# MDL_FUENTE_5V.net
KiCad netlist of a schematic drawn in Altium Designer
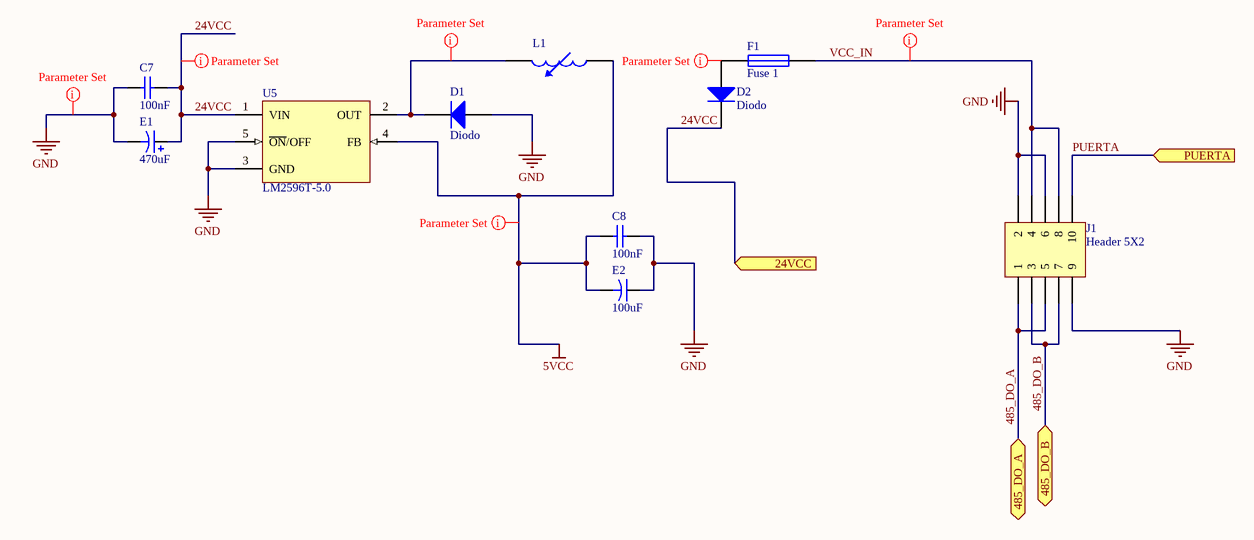
[diagram p0: MDL_FUENTE_5V.SchDoc]

(export (version "E")
  (design (tool "Eeschema 10.0.6"))
  (components
    (comp (ref "C7")
      (value "100nF")
      (footprint "VP44-2.5")
      (description "Dipped Radial Multilayer Ceramic Capacitor X7R: 220nF, 100V")
      (fields (field (name "Comment") "VP44BY224JB") (field (name "PUBLISHER") "Altium Limited"))
      (libsource (lib "Vishay Vitramon Ceramic Dipped Capacitor") (part "VP44BY224JB"))
    )
    (comp (ref "C8")
      (value "100nF")
      (footprint "VP44-2.5")
      (description "Dipped Radial Multilayer Ceramic Capacitor X7R: 220nF, 100V")
      (fields (field (name "Comment") "VP44BY224JB") (field (name "PUBLISHER") "Altium Limited"))
      (libsource (lib "Vishay Vitramon Ceramic Dipped Capacitor") (part "VP44BY224JB"))
    )
    (comp (ref "D1")
      (value "Diodo")
      (footprint "1N4000")
      (description "Diodo rectificador")
      (libsource (lib "Diodos") (part "Diodo"))
    )
    (comp (ref "D2")
      (value "Diodo")
      (footprint "1N4000")
      (description "Diodo rectificador")
      (libsource (lib "Diodos") (part "Diodo"))
    )
    (comp (ref "E1")
      (value "470uF")
      (footprint "C1000UF")
      (description "Polarized Capacitor (Radial)")
      (fields (field (name "Comment") "Cap Pol1") (field (name "PUBLISHER") "Altium Limited"))
      (libsource (lib "Miscellaneous Devices") (part "Cap Pol1"))
    )
    (comp (ref "E2")
      (value "100uF")
      (footprint "C1UF")
      (description "Capacitor")
      (fields (field (name "Comment") "Cap2") (field (name "PUBLISHER") "Altium Limited"))
      (libsource (lib "Miscellaneous Devices") (part "Cap2"))
    )
    (comp (ref "F1")
      (value "Fuse 1")
      (footprint "FUSIBLE_BUSMATIC")
      (description "Fuse")
      (fields (field (name "PUBLISHER") "Altium Limited"))
      (libsource (lib "Miscellaneous Devices") (part "Fuse 1"))
    )
    (comp (ref "J1")
      (value "Header 5X2")
      (footprint "FP_CON10")
      (description "Header, 5-Pin, Dual row")
      (fields (field (name "PUBLISHER") "Altium Limited"))
      (libsource (lib "Miscellaneous Connectors") (part "Header 5X2"))
    )
    (comp (ref "L1")
      (value "Inductor Adj")
      (footprint "Inductor_redondo")
      (description "Adjustable Inductor")
      (fields (field (name "PUBLISHER") "Altium Limited"))
      (libsource (lib "Miscellaneous Devices") (part "Inductor Adj"))
    )
    (comp (ref "U5")
      (value "LM2596T-5.0")
      (footprint "FP_LM2596_D_PCB")
      (description "SIMPLE SWITCHER Power Converter 150 KHz 3A Step-Down Voltage Regulator")
      (fields
        (field (name "MANUFACTURER") "National Semiconductor")
        (field (name "DIGIKEYPARTNUMBER") "LM2596T-5.0-ND")
        (field (name "PUBLISHER") "Altium Limited")
      )
      (libsource (lib "NSC Switcher") (part "LM2596T-5.0"))
    )
  )
  (nets
    (net (code "1") (name "/24VCC") (class "Default")
      (node (ref "C7") (pin "1") (pinfunction "1_1") (pintype "passive"))
      (node (ref "D2") (pin "2") (pinfunction "K_2") (pintype "passive"))
      (node (ref "E1") (pin "1") (pinfunction "1_1") (pintype "passive"))
      (node (ref "U5") (pin "1") (pinfunction "VIN_1") (pintype "power_in"))
    )
    (net (code "2") (name "/485_DO_A") (class "Default")
      (node (ref "J1") (pin "1") (pinfunction "1_1") (pintype "passive"))
      (node (ref "J1") (pin "5") (pinfunction "5_5") (pintype "passive"))
    )
    (net (code "3") (name "/485_DO_B") (class "Default")
      (node (ref "J1") (pin "3") (pinfunction "3_3") (pintype "passive"))
      (node (ref "J1") (pin "7") (pinfunction "7_7") (pintype "passive"))
    )
    (net (code "4") (name "/PUERTA") (class "Default")
      (node (ref "J1") (pin "10") (pinfunction "10_10") (pintype "passive"))
    )
    (net (code "5") (name "/VCC_IN") (class "Default")
      (node (ref "F1") (pin "2") (pinfunction "2_2") (pintype "passive"))
      (node (ref "J1") (pin "4") (pinfunction "4_4") (pintype "passive"))
      (node (ref "J1") (pin "8") (pinfunction "8_8") (pintype "passive"))
    )
    (net (code "6") (name "5VCC") (class "Default")
      (node (ref "C8") (pin "2") (pinfunction "2_2") (pintype "passive"))
      (node (ref "E2") (pin "2") (pinfunction "2_2") (pintype "passive"))
      (node (ref "L1") (pin "1") (pinfunction "1_1") (pintype "passive"))
      (node (ref "U5") (pin "4") (pinfunction "FB_4") (pintype "input"))
    )
    (net (code "7") (name "GND") (class "Default")
      (node (ref "C7") (pin "2") (pinfunction "2_2") (pintype "passive"))
      (node (ref "C8") (pin "1") (pinfunction "1_1") (pintype "passive"))
      (node (ref "D1") (pin "1") (pinfunction "A_1") (pintype "passive"))
      (node (ref "E1") (pin "2") (pinfunction "2_2") (pintype "passive"))
      (node (ref "E2") (pin "1") (pinfunction "1_1") (pintype "passive"))
      (node (ref "J1") (pin "2") (pinfunction "2_2") (pintype "passive"))
      (node (ref "J1") (pin "6") (pinfunction "6_6") (pintype "passive"))
      (node (ref "J1") (pin "9") (pinfunction "9_9") (pintype "passive"))
      (node (ref "U5") (pin "3") (pinfunction "GND_3") (pintype "power_in"))
      (node (ref "U5") (pin "5") (pinfunction "~{ON}/OFF_5") (pintype "input"))
    )
    (net (code "8") (name "Net-(D1-K)") (class "Default")
      (node (ref "D1") (pin "2") (pinfunction "K_2") (pintype "passive"))
      (node (ref "L1") (pin "2") (pinfunction "2_2") (pintype "passive"))
      (node (ref "U5") (pin "2") (pinfunction "OUT_2") (pintype "power_in"))
    )
    (net (code "9") (name "Net-(D2-A)") (class "Default")
      (node (ref "D2") (pin "1") (pinfunction "A_1") (pintype "passive"))
      (node (ref "F1") (pin "1") (pinfunction "1_1") (pintype "passive"))
    )
  )
)
